# main.net
KiCad netlist of a schematic drawn in EAGLE
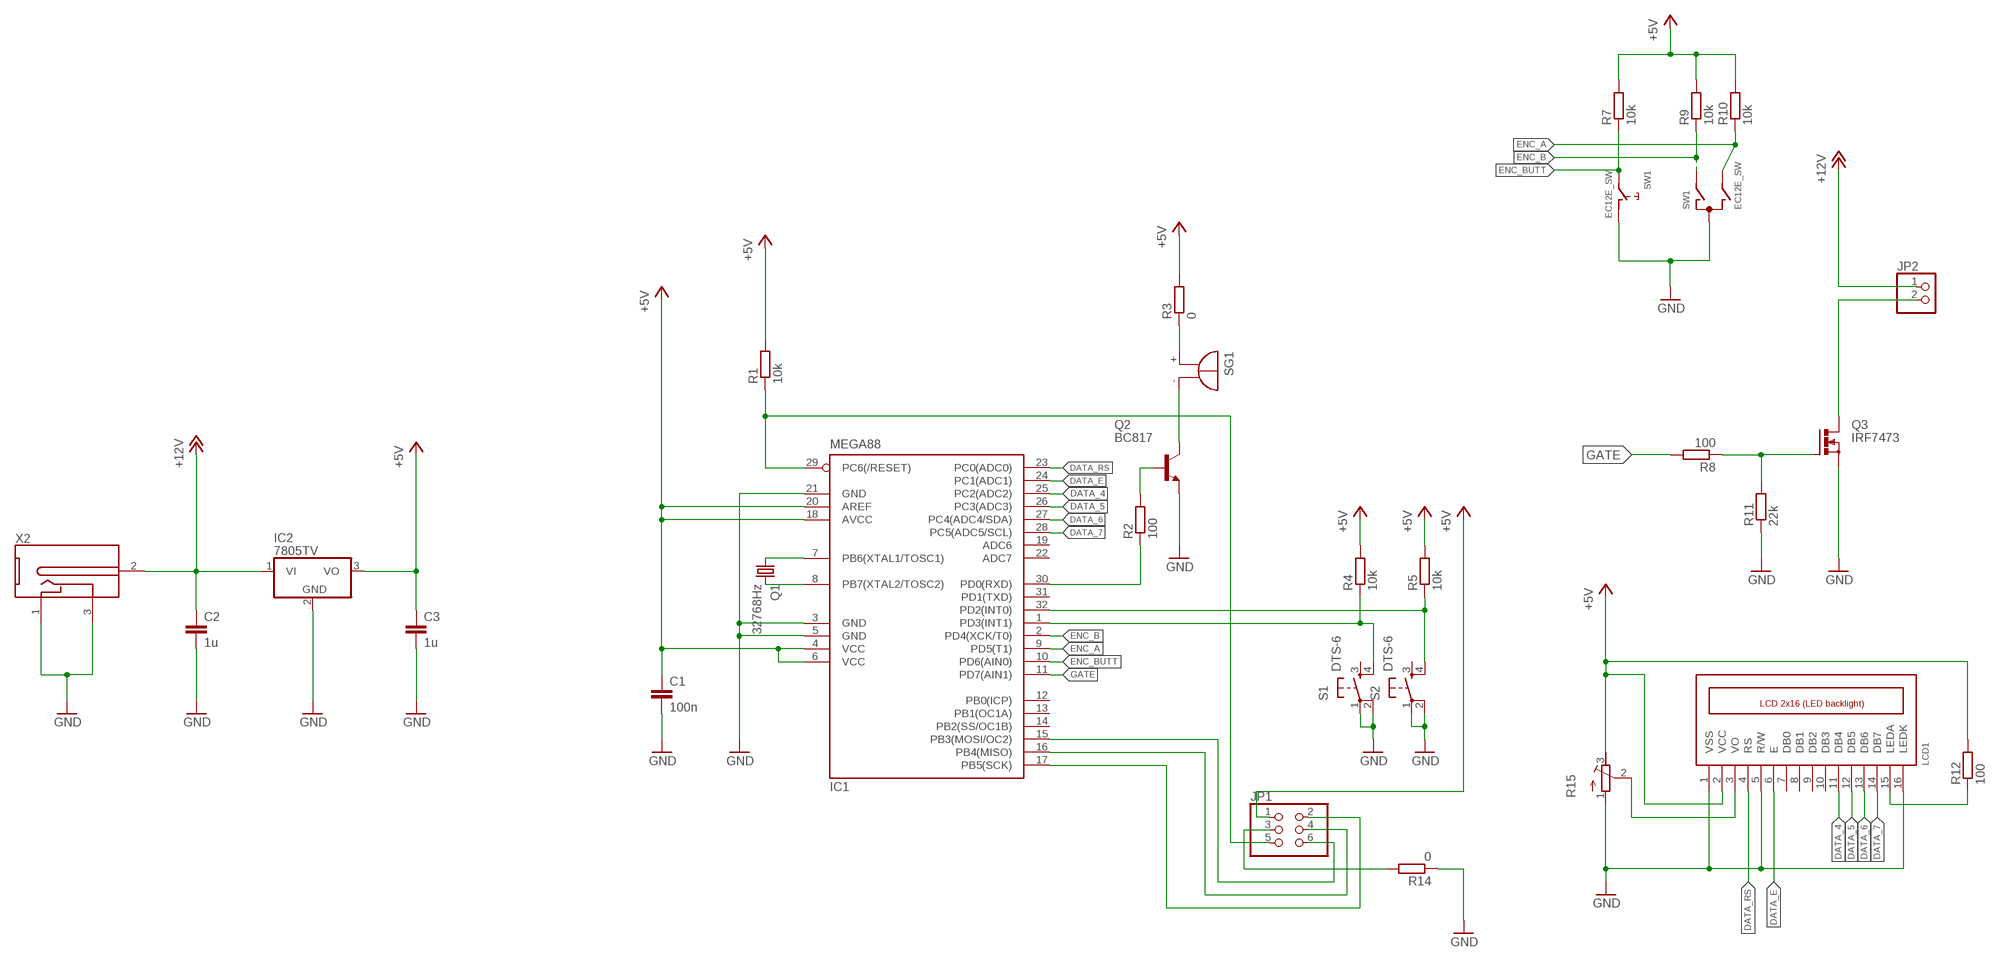
[diagram p0: schematic, sheet 1]

(export (version "E")
  (design (tool "Eeschema 10.0.6"))
  (components
    (comp (ref "C1")
      (value "100n")
      (footprint "eagle-import:C1206K")
      (libsource (lib "eagle-import") (part "C-EUC1206K"))
    )
    (comp (ref "C2")
      (value "1u")
      (footprint "eagle-import:C1206K")
      (libsource (lib "eagle-import") (part "C-EUC1206K"))
    )
    (comp (ref "C3")
      (value "1u")
      (footprint "eagle-import:C1206K")
      (libsource (lib "eagle-import") (part "C-EUC1206K"))
    )
    (comp (ref "IC1")
      (value "MEGA88")
      (footprint "eagle-import:TQFP32-08")
      (fields (field (name "MPN") "ATMEGA8-16AU"))
      (libsource (lib "eagle-import") (part "MEGA8-AI"))
    )
    (comp (ref "IC2")
      (value "7805TV")
      (footprint "eagle-import:TO220V")
      (libsource (lib "eagle-import") (part "78TV05"))
    )
    (comp (ref "JP1")
      (value "PINHD-2X3")
      (footprint "eagle-import:2X03")
      (libsource (lib "eagle-import") (part "PINHD-2X3"))
    )
    (comp (ref "JP2")
      (value "PINHD-1X2")
      (footprint "eagle-import:1X02")
      (libsource (lib "eagle-import") (part "PINHD-1X2"))
    )
    (comp (ref "LCD1")
      (value "LCD_2X16_SIL")
      (footprint "eagle-import:HY-1602F")
      (libsource (lib "eagle-import") (part "LCD_2X16_SIL"))
    )
    (comp (ref "Q1")
      (value "32768Hz")
      (footprint "eagle-import:TC38H")
      (libsource (lib "eagle-import") (part "CRYSTALTC38H"))
    )
    (comp (ref "Q2")
      (value "BC817")
      (footprint "eagle-import:SOT23-BEC")
      (libsource (lib "eagle-import") (part "BC817SMD-16LT1"))
    )
    (comp (ref "Q3")
      (value "IRF7473")
      (footprint "eagle-import:SO-08")
      (libsource (lib "eagle-import") (part "N-MOSFET-SO8S"))
    )
    (comp (ref "R1")
      (value "10k")
      (footprint "eagle-import:R1206")
      (libsource (lib "eagle-import") (part "R-EU_R1206"))
    )
    (comp (ref "R2")
      (value "100")
      (footprint "eagle-import:R1206")
      (libsource (lib "eagle-import") (part "R-EU_R1206"))
    )
    (comp (ref "R3")
      (value "0")
      (footprint "eagle-import:R1206")
      (libsource (lib "eagle-import") (part "R-EU_R1206"))
    )
    (comp (ref "R4")
      (value "10k")
      (footprint "eagle-import:R1206")
      (libsource (lib "eagle-import") (part "R-EU_R1206"))
    )
    (comp (ref "R5")
      (value "10k")
      (footprint "eagle-import:R1206")
      (libsource (lib "eagle-import") (part "R-EU_R1206"))
    )
    (comp (ref "R7")
      (value "10k")
      (footprint "eagle-import:R1206")
      (libsource (lib "eagle-import") (part "R-EU_R1206"))
    )
    (comp (ref "R8")
      (value "100")
      (footprint "eagle-import:R1206")
      (libsource (lib "eagle-import") (part "R-EU_R1206"))
    )
    (comp (ref "R9")
      (value "10k")
      (footprint "eagle-import:R1206")
      (libsource (lib "eagle-import") (part "R-EU_R1206"))
    )
    (comp (ref "R10")
      (value "10k")
      (footprint "eagle-import:R1206")
      (libsource (lib "eagle-import") (part "R-EU_R1206"))
    )
    (comp (ref "R11")
      (value "22k")
      (footprint "eagle-import:R1206")
      (libsource (lib "eagle-import") (part "R-EU_R1206"))
    )
    (comp (ref "R12")
      (value "100")
      (footprint "eagle-import:R1206")
      (libsource (lib "eagle-import") (part "R-EU_R1206"))
    )
    (comp (ref "R14")
      (value "0")
      (footprint "eagle-import:R1206")
      (libsource (lib "eagle-import") (part "R-EU_R1206"))
    )
    (comp (ref "R15")
      (value "R-TRIMM3296W")
      (footprint "eagle-import:RTRIM3296W")
      (libsource (lib "eagle-import") (part "R-TRIMM3296W"))
    )
    (comp (ref "S1")
      (value "DTS-6")
      (footprint "eagle-import:DTS-6")
      (libsource (lib "eagle-import") (part "DTS-6"))
    )
    (comp (ref "S2")
      (value "DTS-6")
      (footprint "eagle-import:DTS-6")
      (libsource (lib "eagle-import") (part "DTS-6"))
    )
    (comp (ref "SG1")
      (value "BMT1205XH7.5")
      (footprint "eagle-import:BMT1205XH7.5")
      (libsource (lib "eagle-import") (part "BMT1205XH7.5"))
    )
    (comp (ref "SW1")
      (value "EC12E_SW")
      (footprint "eagle-import:ALPS_EC12E_SW")
      (fields (field (name "MPN") "EC12E2424407"))
      (libsource (lib "eagle-import") (part "EC12E_SW"))
    )
    (comp (ref "X2")
      (value "DC-2.5MM-5MM")
      (footprint "eagle-import:DC-21MM")
      (libsource (lib "eagle-import") (part "DC-5MM-2.5MM"))
    )
  )
  (nets
    (net (code "1") (name "+5V") (class "Default")
      (node (ref "C1") (pin "1") (pinfunction "1_1") (pintype "passive"))
      (node (ref "C3") (pin "1") (pinfunction "1_1") (pintype "passive"))
      (node (ref "IC1") (pin "18") (pinfunction "AVCC_18") (pintype "power_in"))
      (node (ref "IC1") (pin "20") (pinfunction "AREF_20") (pintype "passive"))
      (node (ref "IC1") (pin "4") (pinfunction "VCC_4") (pintype "power_in"))
      (node (ref "IC1") (pin "6") (pinfunction "VCC_6") (pintype "power_in"))
      (node (ref "IC2") (pin "3") (pinfunction "VO_3") (pintype "passive"))
      (node (ref "JP1") (pin "1") (pinfunction "1_1") (pintype "passive"))
      (node (ref "LCD1") (pin "2") (pinfunction "VCC_2") (pintype "power_in"))
      (node (ref "R1") (pin "2") (pinfunction "2_2") (pintype "passive"))
      (node (ref "R10") (pin "2") (pinfunction "2_2") (pintype "passive"))
      (node (ref "R12") (pin "2") (pinfunction "2_2") (pintype "passive"))
      (node (ref "R15") (pin "3") (pinfunction "E_3") (pintype "passive"))
      (node (ref "R3") (pin "2") (pinfunction "2_2") (pintype "passive"))
      (node (ref "R4") (pin "2") (pinfunction "2_2") (pintype "passive"))
      (node (ref "R5") (pin "2") (pinfunction "2_2") (pintype "passive"))
      (node (ref "R7") (pin "2") (pinfunction "2_2") (pintype "passive"))
      (node (ref "R9") (pin "2") (pinfunction "2_2") (pintype "passive"))
    )
    (net (code "2") (name "+12V") (class "Default")
      (node (ref "C2") (pin "1") (pinfunction "1_1") (pintype "passive"))
      (node (ref "IC2") (pin "1") (pinfunction "VI_1") (pintype "input"))
      (node (ref "JP2") (pin "1") (pinfunction "1_1") (pintype "passive"))
      (node (ref "X2") (pin "2") (pinfunction "3_2") (pintype "power_in"))
    )
    (net (code "3") (name "DATA_4") (class "Default")
      (node (ref "IC1") (pin "25") (pinfunction "PC2(ADC2)_25") (pintype "bidirectional"))
      (node (ref "LCD1") (pin "11") (pinfunction "DB4_11") (pintype "bidirectional"))
    )
    (net (code "4") (name "DATA_5") (class "Default")
      (node (ref "IC1") (pin "26") (pinfunction "PC3(ADC3)_26") (pintype "bidirectional"))
      (node (ref "LCD1") (pin "12") (pinfunction "DB5_12") (pintype "bidirectional"))
    )
    (net (code "5") (name "DATA_6") (class "Default")
      (node (ref "IC1") (pin "27") (pinfunction "PC4(ADC4/SDA)_27") (pintype "bidirectional"))
      (node (ref "LCD1") (pin "13") (pinfunction "DB6_13") (pintype "bidirectional"))
    )
    (net (code "6") (name "DATA_7") (class "Default")
      (node (ref "IC1") (pin "28") (pinfunction "PC5(ADC5/SCL)_28") (pintype "bidirectional"))
      (node (ref "LCD1") (pin "14") (pinfunction "DB7_14") (pintype "bidirectional"))
    )
    (net (code "7") (name "DATA_E") (class "Default")
      (node (ref "IC1") (pin "24") (pinfunction "PC1(ADC1)_24") (pintype "bidirectional"))
      (node (ref "LCD1") (pin "6") (pinfunction "E_6") (pintype "input"))
    )
    (net (code "8") (name "DATA_RS") (class "Default")
      (node (ref "IC1") (pin "23") (pinfunction "PC0(ADC0)_23") (pintype "bidirectional"))
      (node (ref "LCD1") (pin "4") (pinfunction "RS_4") (pintype "input"))
    )
    (net (code "9") (name "ENC_A") (class "Default")
      (node (ref "IC1") (pin "9") (pinfunction "PD5(T1)_9") (pintype "bidirectional"))
      (node (ref "R10") (pin "1") (pinfunction "1_1") (pintype "passive"))
      (node (ref "SW1") (pin "B") (pinfunction "B_B") (pintype "passive"))
    )
    (net (code "10") (name "ENC_B") (class "Default")
      (node (ref "IC1") (pin "2") (pinfunction "PD4(XCK/T0)_2") (pintype "bidirectional"))
      (node (ref "R9") (pin "1") (pinfunction "1_1") (pintype "passive"))
      (node (ref "SW1") (pin "A") (pinfunction "A_A") (pintype "passive"))
    )
    (net (code "11") (name "ENC_BUTT") (class "Default")
      (node (ref "IC1") (pin "10") (pinfunction "PD6(AIN0)_10") (pintype "bidirectional"))
      (node (ref "R7") (pin "1") (pinfunction "1_1") (pintype "passive"))
      (node (ref "SW1") (pin "E") (pinfunction "BUTT_E") (pintype "passive"))
    )
    (net (code "12") (name "GATE") (class "Default")
      (node (ref "IC1") (pin "11") (pinfunction "PD7(AIN1)_11") (pintype "bidirectional"))
      (node (ref "R8") (pin "2") (pinfunction "2_2") (pintype "passive"))
    )
    (net (code "13") (name "GND") (class "Default")
      (node (ref "C1") (pin "2") (pinfunction "2_2") (pintype "passive"))
      (node (ref "C2") (pin "2") (pinfunction "2_2") (pintype "passive"))
      (node (ref "C3") (pin "2") (pinfunction "2_2") (pintype "passive"))
      (node (ref "IC1") (pin "21") (pinfunction "GND_21") (pintype "power_in"))
      (node (ref "IC1") (pin "3") (pinfunction "GND_3") (pintype "power_in"))
      (node (ref "IC1") (pin "5") (pinfunction "GND_5") (pintype "power_in"))
      (node (ref "IC2") (pin "2") (pinfunction "GND_2") (pintype "passive"))
      (node (ref "LCD1") (pin "1") (pinfunction "VSS_1") (pintype "power_in"))
      (node (ref "LCD1") (pin "16") (pinfunction "LEDK_16") (pintype "passive"))
      (node (ref "LCD1") (pin "5") (pinfunction "R/W_5") (pintype "input"))
      (node (ref "Q2") (pin "E") (pinfunction "E_E") (pintype "passive"))
      (node (ref "Q3") (pin "1") (pinfunction "S_1") (pintype "passive"))
      (node (ref "Q3") (pin "2") (pinfunction "S_2") (pintype "passive"))
      (node (ref "Q3") (pin "3") (pinfunction "S_3") (pintype "passive"))
      (node (ref "R11") (pin "1") (pinfunction "1_1") (pintype "passive"))
      (node (ref "R14") (pin "1") (pinfunction "1_1") (pintype "passive"))
      (node (ref "R15") (pin "1") (pinfunction "A_1") (pintype "passive"))
      (node (ref "S1") (pin "1") (pinfunction "1_1") (pintype "passive"))
      (node (ref "S1") (pin "2") (pinfunction "2_2") (pintype "passive"))
      (node (ref "S2") (pin "1") (pinfunction "1_1") (pintype "passive"))
      (node (ref "S2") (pin "2") (pinfunction "2_2") (pintype "passive"))
      (node (ref "SW1") (pin "C") (pinfunction "C_C") (pintype "passive"))
      (node (ref "SW1") (pin "GND@1") (pinfunction "BUTT_GND_GND@1") (pintype "passive"))
      (node (ref "X2") (pin "1") (pinfunction "1_1") (pintype "power_in"))
      (node (ref "X2") (pin "3") (pinfunction "2_3") (pintype "power_in"))
    )
    (net (code "14") (name "Net-(IC1-PB3(MOSI{slash}OC2))") (class "Default")
      (node (ref "IC1") (pin "15") (pinfunction "PB3(MOSI/OC2)_15") (pintype "bidirectional"))
      (node (ref "JP1") (pin "6") (pinfunction "6_6") (pintype "passive"))
    )
    (net (code "15") (name "Net-(IC1-PB4(MISO))") (class "Default")
      (node (ref "IC1") (pin "16") (pinfunction "PB4(MISO)_16") (pintype "bidirectional"))
      (node (ref "JP1") (pin "4") (pinfunction "4_4") (pintype "passive"))
    )
    (net (code "16") (name "Net-(IC1-PB5(SCK))") (class "Default")
      (node (ref "IC1") (pin "17") (pinfunction "PB5(SCK)_17") (pintype "bidirectional"))
      (node (ref "JP1") (pin "2") (pinfunction "2_2") (pintype "passive"))
    )
    (net (code "17") (name "Net-(IC1-PB6(XTAL1{slash}TOSC1))") (class "Default")
      (node (ref "IC1") (pin "7") (pinfunction "PB6(XTAL1/TOSC1)_7") (pintype "bidirectional"))
      (node (ref "Q1") (pin "1") (pinfunction "1_1") (pintype "passive"))
    )
    (net (code "18") (name "Net-(IC1-PB7(XTAL2{slash}TOSC2))") (class "Default")
      (node (ref "IC1") (pin "8") (pinfunction "PB7(XTAL2/TOSC2)_8") (pintype "bidirectional"))
      (node (ref "Q1") (pin "2") (pinfunction "2_2") (pintype "passive"))
    )
    (net (code "19") (name "Net-(IC1-PC6({slash}RESET))") (class "Default")
      (node (ref "IC1") (pin "29") (pinfunction "PC6(/RESET)_29") (pintype "bidirectional"))
      (node (ref "JP1") (pin "5") (pinfunction "5_5") (pintype "passive"))
      (node (ref "R1") (pin "1") (pinfunction "1_1") (pintype "passive"))
    )
    (net (code "20") (name "Net-(IC1-PD0(RXD))") (class "Default")
      (node (ref "IC1") (pin "30") (pinfunction "PD0(RXD)_30") (pintype "bidirectional"))
      (node (ref "R2") (pin "1") (pinfunction "1_1") (pintype "passive"))
    )
    (net (code "21") (name "Net-(IC1-PD2(INT0))") (class "Default")
      (node (ref "IC1") (pin "32") (pinfunction "PD2(INT0)_32") (pintype "bidirectional"))
      (node (ref "R5") (pin "1") (pinfunction "1_1") (pintype "passive"))
      (node (ref "S2") (pin "4") (pinfunction "4_4") (pintype "passive"))
    )
    (net (code "22") (name "Net-(IC1-PD3(INT1))") (class "Default")
      (node (ref "IC1") (pin "1") (pinfunction "PD3(INT1)_1") (pintype "bidirectional"))
      (node (ref "R4") (pin "1") (pinfunction "1_1") (pintype "passive"))
      (node (ref "S1") (pin "4") (pinfunction "4_4") (pintype "passive"))
    )
    (net (code "23") (name "Net-(JP1-Pad3)") (class "Default")
      (node (ref "JP1") (pin "3") (pinfunction "3_3") (pintype "passive"))
      (node (ref "R14") (pin "2") (pinfunction "2_2") (pintype "passive"))
    )
    (net (code "24") (name "Net-(JP2-Pad2)") (class "Default")
      (node (ref "JP2") (pin "2") (pinfunction "2_2") (pintype "passive"))
      (node (ref "Q3") (pin "5") (pinfunction "D_5") (pintype "passive"))
      (node (ref "Q3") (pin "6") (pinfunction "D_6") (pintype "passive"))
      (node (ref "Q3") (pin "7") (pinfunction "D_7") (pintype "passive"))
      (node (ref "Q3") (pin "8") (pinfunction "D_8") (pintype "passive"))
    )
    (net (code "25") (name "Net-(LCD1-LEDA)") (class "Default")
      (node (ref "LCD1") (pin "15") (pinfunction "LEDA_15") (pintype "passive"))
      (node (ref "R12") (pin "1") (pinfunction "1_1") (pintype "passive"))
    )
    (net (code "26") (name "Net-(LCD1-VO)") (class "Default")
      (node (ref "LCD1") (pin "3") (pinfunction "VO_3") (pintype "input"))
      (node (ref "R15") (pin "2") (pinfunction "S_2") (pintype "passive"))
    )
    (net (code "27") (name "Net-(Q2-PadB)") (class "Default")
      (node (ref "Q2") (pin "B") (pinfunction "B_B") (pintype "passive"))
      (node (ref "R2") (pin "2") (pinfunction "2_2") (pintype "passive"))
    )
    (net (code "28") (name "Net-(Q2-PadC)") (class "Default")
      (node (ref "Q2") (pin "C") (pinfunction "C_C") (pintype "passive"))
      (node (ref "SG1") (pin "-") (pinfunction "-_-") (pintype "passive"))
    )
    (net (code "29") (name "Net-(Q3-G)") (class "Default")
      (node (ref "Q3") (pin "4") (pinfunction "G_4") (pintype "passive"))
      (node (ref "R11") (pin "2") (pinfunction "2_2") (pintype "passive"))
      (node (ref "R8") (pin "1") (pinfunction "1_1") (pintype "passive"))
    )
    (net (code "30") (name "Net-(R3-Pad1)") (class "Default")
      (node (ref "R3") (pin "1") (pinfunction "1_1") (pintype "passive"))
      (node (ref "SG1") (pin "+") (pinfunction "+_+") (pintype "passive"))
    )
    (net (code "31") (name "unconnected-(IC1-ADC6-Pad19)") (class "Default")
      (node (ref "IC1") (pin "19") (pinfunction "ADC6_19") (pintype "bidirectional"))
    )
    (net (code "32") (name "unconnected-(IC1-ADC7-Pad22)") (class "Default")
      (node (ref "IC1") (pin "22") (pinfunction "ADC7_22") (pintype "bidirectional"))
    )
    (net (code "33") (name "unconnected-(IC1-PB0(ICP)-Pad12)") (class "Default")
      (node (ref "IC1") (pin "12") (pinfunction "PB0(ICP)_12") (pintype "bidirectional"))
    )
    (net (code "34") (name "unconnected-(IC1-PB1(OC1A)-Pad13)") (class "Default")
      (node (ref "IC1") (pin "13") (pinfunction "PB1(OC1A)_13") (pintype "bidirectional"))
    )
    (net (code "35") (name "unconnected-(IC1-PB2(SS{slash}OC1B)-Pad14)") (class "Default")
      (node (ref "IC1") (pin "14") (pinfunction "PB2(SS/OC1B)_14") (pintype "bidirectional"))
    )
    (net (code "36") (name "unconnected-(IC1-PD1(TXD)-Pad31)") (class "Default")
      (node (ref "IC1") (pin "31") (pinfunction "PD1(TXD)_31") (pintype "bidirectional"))
    )
    (net (code "37") (name "unconnected-(LCD1-DB0-Pad7)") (class "Default")
      (node (ref "LCD1") (pin "7") (pinfunction "DB0_7") (pintype "bidirectional"))
    )
    (net (code "38") (name "unconnected-(LCD1-DB1-Pad8)") (class "Default")
      (node (ref "LCD1") (pin "8") (pinfunction "DB1_8") (pintype "bidirectional"))
    )
    (net (code "39") (name "unconnected-(LCD1-DB2-Pad9)") (class "Default")
      (node (ref "LCD1") (pin "9") (pinfunction "DB2_9") (pintype "bidirectional"))
    )
    (net (code "40") (name "unconnected-(LCD1-DB3-Pad10)") (class "Default")
      (node (ref "LCD1") (pin "10") (pinfunction "DB3_10") (pintype "bidirectional"))
    )
    (net (code "41") (name "unconnected-(S1-Pad3)") (class "Default")
      (node (ref "S1") (pin "3") (pinfunction "3_3") (pintype "passive"))
    )
    (net (code "42") (name "unconnected-(S2-Pad3)") (class "Default")
      (node (ref "S2") (pin "3") (pinfunction "3_3") (pintype "passive"))
    )
  )
)
